# Power_Switching_Circuit_rev2.net
KiCad netlist of a schematic drawn in EAGLE
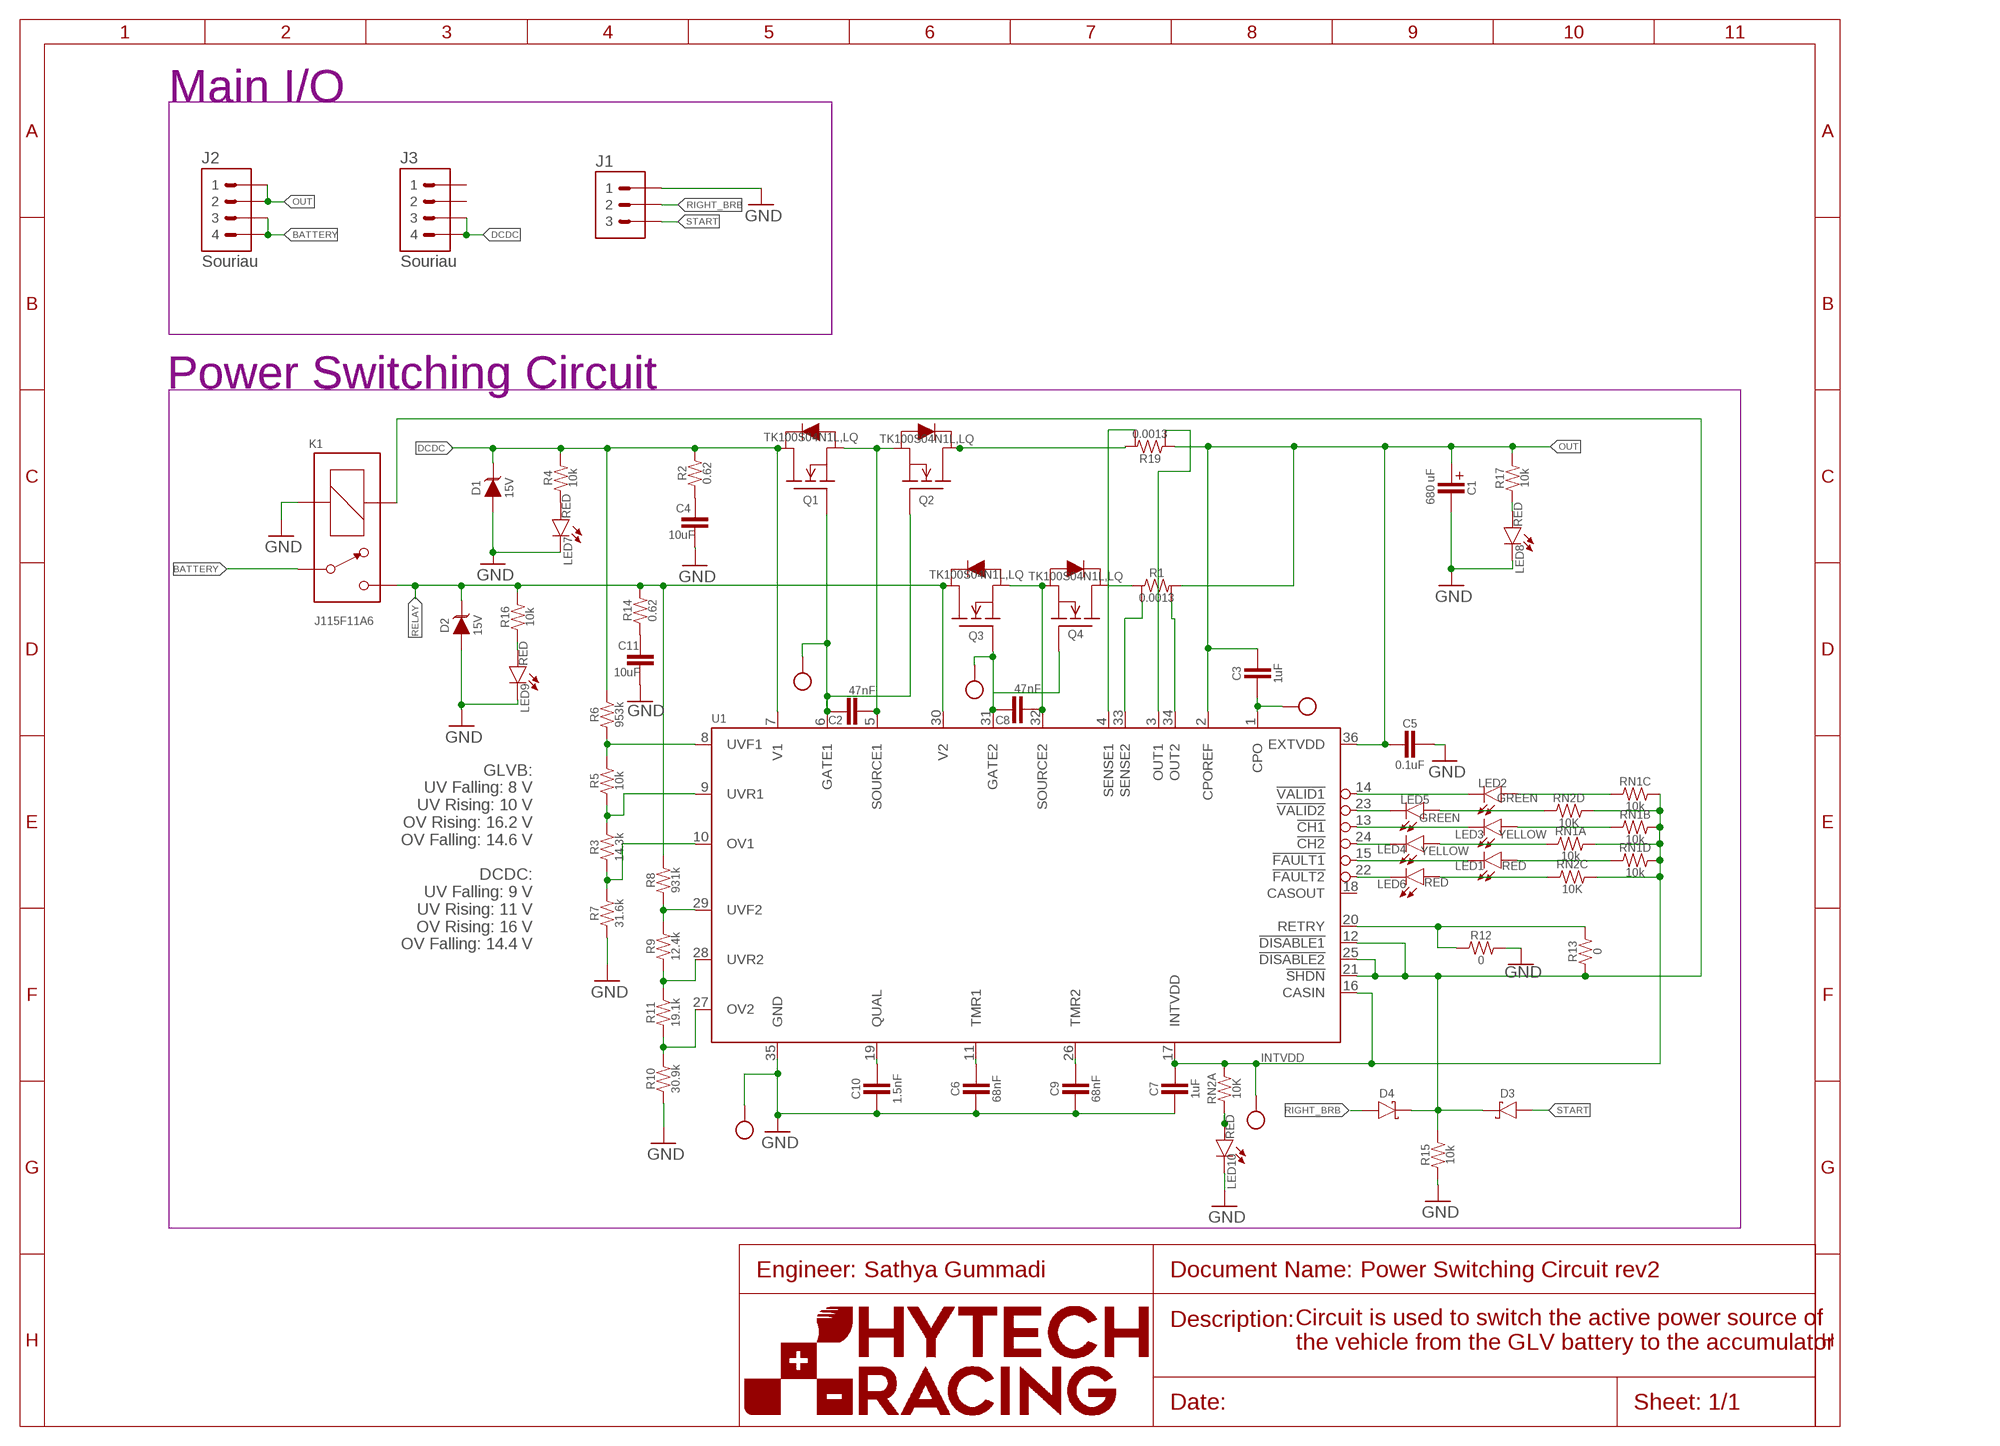
[diagram p0: schematic, sheet 1]

(export (version "E")
  (design (tool "Eeschema 10.0.6"))
  (components
    (comp (ref "C1")
      (value "CAPACITOR_POLARIZED")
      (footprint "eagle-import:EEE-FK1H681AM")
      (libsource (lib "eagle-import") (part "CAPACITOR_POLARIZED"))
    )
    (comp (ref "C2")
      (value "47nF")
      (footprint "eagle-import:0603-CAP@1")
      (libsource (lib "eagle-import") (part "CAP0603-CAP"))
    )
    (comp (ref "C3")
      (value "1uF")
      (footprint "eagle-import:0805")
      (libsource (lib "eagle-import") (part "CAP0805"))
    )
    (comp (ref "C4")
      (value "10uF")
      (footprint "eagle-import:1206-CAP")
      (libsource (lib "eagle-import") (part "CAPACITOR_VALUE1206"))
    )
    (comp (ref "C5")
      (value "0.1uF")
      (footprint "eagle-import:0603-CAP@1")
      (libsource (lib "eagle-import") (part "CAP0603-CAP"))
    )
    (comp (ref "C6")
      (value "68nF")
      (footprint "eagle-import:0603-CAP@1")
      (libsource (lib "eagle-import") (part "CAP0603-CAP"))
    )
    (comp (ref "C7")
      (value "1uF")
      (footprint "eagle-import:0805")
      (libsource (lib "eagle-import") (part "CAP0805"))
    )
    (comp (ref "C8")
      (value "47nF")
      (footprint "eagle-import:0603-CAP@1")
      (libsource (lib "eagle-import") (part "CAP0603-CAP"))
    )
    (comp (ref "C9")
      (value "68nF")
      (footprint "eagle-import:0603-CAP@1")
      (libsource (lib "eagle-import") (part "CAP0603-CAP"))
    )
    (comp (ref "C10")
      (value "1.5nF")
      (footprint "eagle-import:0603-CAP@1")
      (libsource (lib "eagle-import") (part "CAP0603-CAP"))
    )
    (comp (ref "C11")
      (value "10uF")
      (footprint "eagle-import:1206-CAP")
      (libsource (lib "eagle-import") (part "CAPACITOR_VALUE1206"))
    )
    (comp (ref "D1")
      (value "TVS_15V")
      (footprint "eagle-import:SOT-23")
      (fields
        (field (name "MANUFACTURER") "Vishay General Semiconductor - Diodes Division")
        (field (name "MPN") "GSOT15-E3-08")
        (field (name "VOLTAGE") "15V")
      )
      (libsource (lib "eagle-import") (part "TVS_15V"))
    )
    (comp (ref "D2")
      (value "TVS_15V")
      (footprint "eagle-import:SOT-23")
      (fields
        (field (name "MANUFACTURER") "Vishay General Semiconductor - Diodes Division")
        (field (name "MPN") "GSOT15-E3-08")
        (field (name "VOLTAGE") "15V")
      )
      (libsource (lib "eagle-import") (part "TVS_15V"))
    )
    (comp (ref "D3")
      (value "SCHOTTKY")
      (footprint "eagle-import:CLP1608-2L")
      (fields
        (field (name "MANUFACTURER") "Vishay General Semiconductor - Diodes Division")
        (field (name "MPN") "VSKY20401608-G4-08")
      )
      (libsource (lib "eagle-import") (part "SCHOTTKY"))
    )
    (comp (ref "D4")
      (value "SCHOTTKY")
      (footprint "eagle-import:CLP1608-2L")
      (fields
        (field (name "MANUFACTURER") "Vishay General Semiconductor - Diodes Division")
        (field (name "MPN") "VSKY20401608-G4-08")
      )
      (libsource (lib "eagle-import") (part "SCHOTTKY"))
    )
    (comp (ref "J1")
      (value "CONNECTOR-3_")
      (footprint "eagle-import:SOURIAU_04-35")
      (libsource (lib "eagle-import") (part "CONNECTOR-3_?"))
    )
    (comp (ref "J2")
      (value "CONNECTOR-4_SOURIAU_")
      (footprint "eagle-import:SOURIAU_12-04")
      (fields
        (field (name "MODEL") "Souriau")
        (field (name "MANUFACTURER") "Souriau")
        (field (name "MPN") "8STA21204PN ")
      )
      (libsource (lib "eagle-import") (part "CONNECTOR-4_?_SOURIAU"))
    )
    (comp (ref "J3")
      (value "CONNECTOR-4_SOURIAU_")
      (footprint "eagle-import:SOURIAU_12-04")
      (fields
        (field (name "MODEL") "Souriau")
        (field (name "MANUFACTURER") "Souriau")
        (field (name "MPN") "8STA21204PN ")
      )
      (libsource (lib "eagle-import") (part "CONNECTOR-4_?_SOURIAU"))
    )
    (comp (ref "K1")
      (value "J115F11A6")
      (footprint "eagle-import:J115F11A_6_")
      (libsource (lib "eagle-import") (part "J115F11A6"))
    )
    (comp (ref "LED1")
      (value "RED")
      (footprint "eagle-import:LED-603")
      (libsource (lib "eagle-import") (part "LED-0603"))
    )
    (comp (ref "LED2")
      (value "GREEN")
      (footprint "eagle-import:LED-603")
      (libsource (lib "eagle-import") (part "LED-0603"))
    )
    (comp (ref "LED3")
      (value "YELLOW")
      (footprint "eagle-import:LED-603")
      (libsource (lib "eagle-import") (part "LED-0603"))
    )
    (comp (ref "LED4")
      (value "YELLOW")
      (footprint "eagle-import:LED-603")
      (libsource (lib "eagle-import") (part "LED-0603"))
    )
    (comp (ref "LED5")
      (value "GREEN")
      (footprint "eagle-import:LED-603")
      (libsource (lib "eagle-import") (part "LED-0603"))
    )
    (comp (ref "LED6")
      (value "RED")
      (footprint "eagle-import:LED-603")
      (libsource (lib "eagle-import") (part "LED-0603"))
    )
    (comp (ref "LED7")
      (value "RED")
      (footprint "eagle-import:LED-603")
      (libsource (lib "eagle-import") (part "LED-0603"))
    )
    (comp (ref "LED8")
      (value "RED")
      (footprint "eagle-import:LED-603")
      (libsource (lib "eagle-import") (part "LED-0603"))
    )
    (comp (ref "LED9")
      (value "RED")
      (footprint "eagle-import:LED-603")
      (libsource (lib "eagle-import") (part "LED-0603"))
    )
    (comp (ref "LED10")
      (value "RED")
      (footprint "eagle-import:LED-603")
      (libsource (lib "eagle-import") (part "LED-0603"))
    )
    (comp (ref "Q1")
      (value "TRANSISTOR_N_MOS_2-7K1S_TK100S04N1L,LQ")
      (footprint "eagle-import:DPAK(2-7K1S)")
      (fields
        (field (name "MANUFACTURER") "Toshiba Semiconductor and Storage")
        (field (name "MPN") "TK100S04N1L,LQ")
      )
      (libsource (lib "eagle-import") (part "TRANSISTOR_N_MOS_?_2-7K1STK100S04N1L,LQ"))
    )
    (comp (ref "Q2")
      (value "TRANSISTOR_N_MOS_2-7K1S_TK100S04N1L,LQ")
      (footprint "eagle-import:DPAK(2-7K1S)")
      (fields
        (field (name "MANUFACTURER") "Toshiba Semiconductor and Storage")
        (field (name "MPN") "TK100S04N1L,LQ")
      )
      (libsource (lib "eagle-import") (part "TRANSISTOR_N_MOS_?_2-7K1STK100S04N1L,LQ"))
    )
    (comp (ref "Q3")
      (value "TRANSISTOR_N_MOS_2-7K1S_TK100S04N1L,LQ")
      (footprint "eagle-import:DPAK(2-7K1S)")
      (fields
        (field (name "MANUFACTURER") "Toshiba Semiconductor and Storage")
        (field (name "MPN") "TK100S04N1L,LQ")
      )
      (libsource (lib "eagle-import") (part "TRANSISTOR_N_MOS_?_2-7K1STK100S04N1L,LQ"))
    )
    (comp (ref "Q4")
      (value "TRANSISTOR_N_MOS_2-7K1S_TK100S04N1L,LQ")
      (footprint "eagle-import:DPAK(2-7K1S)")
      (fields
        (field (name "MANUFACTURER") "Toshiba Semiconductor and Storage")
        (field (name "MPN") "TK100S04N1L,LQ")
      )
      (libsource (lib "eagle-import") (part "TRANSISTOR_N_MOS_?_2-7K1STK100S04N1L,LQ"))
    )
    (comp (ref "R1")
      (value "RESISTOR_SENSE")
      (footprint "eagle-import:WSL2726")
      (fields (field (name "RESISTANCE") "0.0013") (field (name "MPN") "WSL2726"))
      (libsource (lib "eagle-import") (part "RESISTOR_SENSE"))
    )
    (comp (ref "R2")
      (value "0.62")
      (footprint "eagle-import:0805")
      (libsource (lib "eagle-import") (part "RESISTOR0805"))
    )
    (comp (ref "R3")
      (value "14.3k")
      (footprint "eagle-import:0603-RES")
      (libsource (lib "eagle-import") (part "RESISTOR0603"))
    )
    (comp (ref "R4")
      (value "10k")
      (footprint "eagle-import:0603-RES")
      (libsource (lib "eagle-import") (part "RESISTOR0603"))
    )
    (comp (ref "R5")
      (value "10k")
      (footprint "eagle-import:0603-RES")
      (libsource (lib "eagle-import") (part "RESISTOR0603"))
    )
    (comp (ref "R6")
      (value "953k")
      (footprint "eagle-import:0603-RES")
      (libsource (lib "eagle-import") (part "RESISTOR0603"))
    )
    (comp (ref "R7")
      (value "31.6k")
      (footprint "eagle-import:0603-RES")
      (libsource (lib "eagle-import") (part "RESISTOR0603"))
    )
    (comp (ref "R8")
      (value "931k")
      (footprint "eagle-import:0603-RES")
      (libsource (lib "eagle-import") (part "RESISTOR0603"))
    )
    (comp (ref "R9")
      (value "12.4k")
      (footprint "eagle-import:0603-RES")
      (libsource (lib "eagle-import") (part "RESISTOR0603"))
    )
    (comp (ref "R10")
      (value "30.9k")
      (footprint "eagle-import:0603-RES")
      (libsource (lib "eagle-import") (part "RESISTOR0603"))
    )
    (comp (ref "R11")
      (value "19.1k")
      (footprint "eagle-import:0603-RES")
      (libsource (lib "eagle-import") (part "RESISTOR0603"))
    )
    (comp (ref "R12")
      (value "0")
      (footprint "eagle-import:0603-RES")
      (libsource (lib "eagle-import") (part "RESISTOR0603"))
    )
    (comp (ref "R13")
      (value "0")
      (footprint "eagle-import:0603-RES")
      (libsource (lib "eagle-import") (part "RESISTOR0603"))
    )
    (comp (ref "R14")
      (value "0.62")
      (footprint "eagle-import:0805")
      (libsource (lib "eagle-import") (part "RESISTOR0805"))
    )
    (comp (ref "R15")
      (value "10k")
      (footprint "eagle-import:0603-RES")
      (libsource (lib "eagle-import") (part "RESISTOR0603"))
    )
    (comp (ref "R16")
      (value "10k")
      (footprint "eagle-import:0603-RES")
      (libsource (lib "eagle-import") (part "RESISTOR0603"))
    )
    (comp (ref "R17")
      (value "10k")
      (footprint "eagle-import:0603-RES")
      (libsource (lib "eagle-import") (part "RESISTOR0603"))
    )
    (comp (ref "R19")
      (value "RESISTOR_SENSE")
      (footprint "eagle-import:WSL2726")
      (fields (field (name "RESISTANCE") "0.0013") (field (name "MPN") "WSL2726"))
      (libsource (lib "eagle-import") (part "RESISTOR_SENSE"))
    )
    (comp (ref "RN1")
      (value "RESISTOR_NETWORK_4_10K")
      (footprint "eagle-import:YC_TC164")
      (fields (field (name "RESISTANCE") "10k"))
      (libsource (lib "eagle-import") (part "HyTechDevices - Copy_RESISTOR_NETWORK_4_10K"))
    )
    (comp (ref "RN2")
      (value "RESISTOR_NETWORK_4_10K")
      (footprint "eagle-import:1206-RES")
      (fields
        (field (name "MANUFACTURER") "Yageo")
        (field (name "MPN") "TC164-FR-0710KL")
        (field (name "POWER") "1/16W")
        (field (name "RESISTANCE") "10K")
      )
      (libsource (lib "eagle-import") (part "RESISTOR_NETWORK_4_10K"))
    )
    (comp (ref "U$7")
      (value "TEST_POINTMICRO_MINIATURE")
      (footprint "eagle-import:MICRO_MINIATURE")
      (libsource (lib "eagle-import") (part "TEST_POINTMICRO_MINIATURE"))
    )
    (comp (ref "U$8")
      (value "TEST_POINTMICRO_MINIATURE")
      (footprint "eagle-import:MICRO_MINIATURE")
      (libsource (lib "eagle-import") (part "TEST_POINTMICRO_MINIATURE"))
    )
    (comp (ref "U$9")
      (value "TEST_POINTMICRO_MINIATURE")
      (footprint "eagle-import:MICRO_MINIATURE")
      (libsource (lib "eagle-import") (part "TEST_POINTMICRO_MINIATURE"))
    )
    (comp (ref "U$10")
      (value "TEST_POINTMICRO_MINIATURE")
      (footprint "eagle-import:MICRO_MINIATURE")
      (libsource (lib "eagle-import") (part "TEST_POINTMICRO_MINIATURE"))
    )
    (comp (ref "U$11")
      (value "TEST_POINTMICRO_MINIATURE")
      (footprint "eagle-import:MICRO_MINIATURE")
      (libsource (lib "eagle-import") (part "TEST_POINTMICRO_MINIATURE"))
    )
    (comp (ref "U1")
      (value "LTC4421")
      (footprint "eagle-import:SSOP-36")
      (libsource (lib "eagle-import") (part "LTC4421"))
    )
  )
  (nets
    (net (code "1") (name "/INTVDD") (class "Default")
      (node (ref "C7") (pin "1") (pinfunction "1_1") (pintype "passive"))
      (node (ref "RN1") (pin "5") (pinfunction "2_5") (pintype "passive"))
      (node (ref "RN1") (pin "6") (pinfunction "2_6") (pintype "passive"))
      (node (ref "RN1") (pin "7") (pinfunction "2_7") (pintype "passive"))
      (node (ref "RN1") (pin "8") (pinfunction "2_8") (pintype "passive"))
      (node (ref "RN2") (pin "5") (pinfunction "2_5") (pintype "passive"))
      (node (ref "RN2") (pin "6") (pinfunction "2_6") (pintype "passive"))
      (node (ref "RN2") (pin "8") (pinfunction "2_8") (pintype "passive"))
      (node (ref "U$8") (pin "P$1") (pinfunction "P$1_P$1") (pintype "bidirectional"))
      (node (ref "U1") (pin "16") (pinfunction "CASIN_16") (pintype "input"))
      (node (ref "U1") (pin "17") (pinfunction "INTVDD_17") (pintype "power_in"))
    )
    (net (code "2") (name "BATTERY") (class "Default")
      (node (ref "J2") (pin "3") (pinfunction "3_3") (pintype "passive"))
      (node (ref "J2") (pin "4") (pinfunction "4_4") (pintype "passive"))
      (node (ref "K1") (pin "CONTACT1") (pinfunction "P_CONTACT1") (pintype "bidirectional"))
    )
    (net (code "3") (name "DCDC") (class "Default")
      (node (ref "D1") (pin "3") (pinfunction "C_3") (pintype "passive"))
      (node (ref "J3") (pin "3") (pinfunction "3_3") (pintype "passive"))
      (node (ref "J3") (pin "4") (pinfunction "4_4") (pintype "passive"))
      (node (ref "Q1") (pin "2") (pinfunction "D_2") (pintype "passive"))
      (node (ref "R2") (pin "2") (pinfunction "2_2") (pintype "passive"))
      (node (ref "R4") (pin "2") (pinfunction "2_2") (pintype "passive"))
      (node (ref "R6") (pin "2") (pinfunction "2_2") (pintype "passive"))
      (node (ref "U1") (pin "7") (pinfunction "V1_7") (pintype "input"))
    )
    (net (code "4") (name "GND") (class "Default")
      (node (ref "C1") (pin "P$2") (pinfunction "MINUS_P$2") (pintype "passive"))
      (node (ref "C10") (pin "2") (pinfunction "2_2") (pintype "passive"))
      (node (ref "C11") (pin "2") (pinfunction "2_2") (pintype "passive"))
      (node (ref "C4") (pin "2") (pinfunction "2_2") (pintype "passive"))
      (node (ref "C5") (pin "1") (pinfunction "1_1") (pintype "passive"))
      (node (ref "C6") (pin "2") (pinfunction "2_2") (pintype "passive"))
      (node (ref "C7") (pin "2") (pinfunction "2_2") (pintype "passive"))
      (node (ref "C9") (pin "2") (pinfunction "2_2") (pintype "passive"))
      (node (ref "D1") (pin "1") (pinfunction "A_1") (pintype "passive"))
      (node (ref "D2") (pin "1") (pinfunction "A_1") (pintype "passive"))
      (node (ref "J1") (pin "A") (pinfunction "1_A") (pintype "passive"))
      (node (ref "K1") (pin "COIL2") (pinfunction "COIL-_COIL2") (pintype "bidirectional"))
      (node (ref "LED10") (pin "C") (pinfunction "C_C") (pintype "passive"))
      (node (ref "LED7") (pin "C") (pinfunction "C_C") (pintype "passive"))
      (node (ref "LED8") (pin "C") (pinfunction "C_C") (pintype "passive"))
      (node (ref "LED9") (pin "C") (pinfunction "C_C") (pintype "passive"))
      (node (ref "R10") (pin "1") (pinfunction "1_1") (pintype "passive"))
      (node (ref "R12") (pin "2") (pinfunction "2_2") (pintype "passive"))
      (node (ref "R15") (pin "1") (pinfunction "1_1") (pintype "passive"))
      (node (ref "R7") (pin "1") (pinfunction "1_1") (pintype "passive"))
      (node (ref "U$11") (pin "P$1") (pinfunction "P$1_P$1") (pintype "bidirectional"))
      (node (ref "U1") (pin "35") (pinfunction "GND_35") (pintype "power_in"))
    )
    (net (code "5") (name "Net-(C4-Pad1)") (class "Default")
      (node (ref "C4") (pin "1") (pinfunction "1_1") (pintype "passive"))
      (node (ref "R2") (pin "1") (pinfunction "1_1") (pintype "passive"))
    )
    (net (code "6") (name "Net-(C11-Pad1)") (class "Default")
      (node (ref "C11") (pin "1") (pinfunction "1_1") (pintype "passive"))
      (node (ref "R14") (pin "1") (pinfunction "1_1") (pintype "passive"))
    )
    (net (code "7") (name "Net-(D3-C)") (class "Default")
      (node (ref "D3") (pin "2") (pinfunction "C_2") (pintype "passive"))
      (node (ref "D4") (pin "2") (pinfunction "C_2") (pintype "passive"))
      (node (ref "K1") (pin "COIL1") (pinfunction "COIL+_COIL1") (pintype "bidirectional"))
      (node (ref "R13") (pin "1") (pinfunction "1_1") (pintype "passive"))
      (node (ref "R15") (pin "2") (pinfunction "2_2") (pintype "passive"))
      (node (ref "U1") (pin "12") (pinfunction "~{DISABLE1}_12") (pintype "input"))
      (node (ref "U1") (pin "21") (pinfunction "~{SHDN}_21") (pintype "input"))
      (node (ref "U1") (pin "25") (pinfunction "~{DISABLE2}_25") (pintype "input"))
    )
    (net (code "8") (name "Net-(LED4-PadA)") (class "Default")
      (node (ref "LED4") (pin "A") (pinfunction "A_A") (pintype "passive"))
      (node (ref "RN1") (pin "1") (pinfunction "1_1") (pintype "passive"))
    )
    (net (code "9") (name "Net-(LED7-PadA)") (class "Default")
      (node (ref "LED7") (pin "A") (pinfunction "A_A") (pintype "passive"))
      (node (ref "R4") (pin "1") (pinfunction "1_1") (pintype "passive"))
    )
    (net (code "10") (name "Net-(LED8-PadA)") (class "Default")
      (node (ref "LED8") (pin "A") (pinfunction "A_A") (pintype "passive"))
      (node (ref "R17") (pin "1") (pinfunction "1_1") (pintype "passive"))
    )
    (net (code "11") (name "Net-(LED9-PadA)") (class "Default")
      (node (ref "LED9") (pin "A") (pinfunction "A_A") (pintype "passive"))
      (node (ref "R16") (pin "1") (pinfunction "1_1") (pintype "passive"))
    )
    (net (code "12") (name "Net-(LED10-PadA)") (class "Default")
      (node (ref "LED10") (pin "A") (pinfunction "A_A") (pintype "passive"))
      (node (ref "RN2") (pin "1") (pinfunction "1_1") (pintype "passive"))
    )
    (net (code "13") (name "Net-(Q1-G)") (class "Default")
      (node (ref "C2") (pin "2") (pinfunction "2_2") (pintype "passive"))
      (node (ref "Q1") (pin "1") (pinfunction "G_1") (pintype "passive"))
      (node (ref "Q2") (pin "1") (pinfunction "G_1") (pintype "passive"))
      (node (ref "U$10") (pin "P$1") (pinfunction "P$1_P$1") (pintype "bidirectional"))
      (node (ref "U1") (pin "6") (pinfunction "GATE1_6") (pintype "input"))
    )
    (net (code "14") (name "Net-(Q1-S)") (class "Default")
      (node (ref "C2") (pin "1") (pinfunction "1_1") (pintype "passive"))
      (node (ref "Q1") (pin "3") (pinfunction "S_3") (pintype "passive"))
      (node (ref "Q2") (pin "3") (pinfunction "S_3") (pintype "passive"))
      (node (ref "U1") (pin "5") (pinfunction "SOURCE1_5") (pintype "input"))
    )
    (net (code "15") (name "Net-(Q2-D)") (class "Default")
      (node (ref "Q2") (pin "2") (pinfunction "D_2") (pintype "passive"))
      (node (ref "R19") (pin "2") (pinfunction "2_2") (pintype "passive"))
    )
    (net (code "16") (name "Net-(Q3-G)") (class "Default")
      (node (ref "C8") (pin "2") (pinfunction "2_2") (pintype "passive"))
      (node (ref "Q3") (pin "1") (pinfunction "G_1") (pintype "passive"))
      (node (ref "Q4") (pin "1") (pinfunction "G_1") (pintype "passive"))
      (node (ref "U$7") (pin "P$1") (pinfunction "P$1_P$1") (pintype "bidirectional"))
      (node (ref "U1") (pin "31") (pinfunction "GATE2_31") (pintype "input"))
    )
    (net (code "17") (name "Net-(Q3-S)") (class "Default")
      (node (ref "C8") (pin "1") (pinfunction "1_1") (pintype "passive"))
      (node (ref "Q3") (pin "3") (pinfunction "S_3") (pintype "passive"))
      (node (ref "Q4") (pin "3") (pinfunction "S_3") (pintype "passive"))
      (node (ref "U1") (pin "32") (pinfunction "SOURCE2_32") (pintype "input"))
    )
    (net (code "18") (name "Net-(Q4-D)") (class "Default")
      (node (ref "Q4") (pin "2") (pinfunction "D_2") (pintype "passive"))
      (node (ref "R1") (pin "1") (pinfunction "1_1") (pintype "passive"))
    )
    (net (code "19") (name "Net-(RN1B-1)") (class "Default")
      (node (ref "LED3") (pin "A") (pinfunction "A_A") (pintype "passive"))
      (node (ref "RN1") (pin "2") (pinfunction "1_2") (pintype "passive"))
    )
    (net (code "20") (name "Net-(RN1C-1)") (class "Default")
      (node (ref "LED2") (pin "A") (pinfunction "A_A") (pintype "passive"))
      (node (ref "RN1") (pin "3") (pinfunction "1_3") (pintype "passive"))
    )
    (net (code "21") (name "Net-(RN1D-1)") (class "Default")
      (node (ref "LED1") (pin "A") (pinfunction "A_A") (pintype "passive"))
      (node (ref "RN1") (pin "4") (pinfunction "1_4") (pintype "passive"))
    )
    (net (code "22") (name "Net-(RN2C-1)") (class "Default")
      (node (ref "LED6") (pin "A") (pinfunction "A_A") (pintype "passive"))
      (node (ref "RN2") (pin "3") (pinfunction "1_3") (pintype "passive"))
    )
    (net (code "23") (name "Net-(RN2D-1)") (class "Default")
      (node (ref "LED5") (pin "A") (pinfunction "A_A") (pintype "passive"))
      (node (ref "RN2") (pin "4") (pinfunction "1_4") (pintype "passive"))
    )
    (net (code "24") (name "Net-(U1-CPO)") (class "Default")
      (node (ref "C3") (pin "2") (pinfunction "2_2") (pintype "passive"))
      (node (ref "U$9") (pin "P$1") (pinfunction "P$1_P$1") (pintype "bidirectional"))
      (node (ref "U1") (pin "1") (pinfunction "CPO_1") (pintype "input"))
    )
    (net (code "25") (name "Net-(U1-OUT1)") (class "Default")
      (node (ref "R19") (pin "3") (pinfunction "3_3") (pintype "passive"))
      (node (ref "U1") (pin "3") (pinfunction "OUT1_3") (pintype "input"))
    )
    (net (code "26") (name "Net-(U1-OUT2)") (class "Default")
      (node (ref "R1") (pin "4") (pinfunction "4_4") (pintype "passive"))
      (node (ref "U1") (pin "34") (pinfunction "OUT2_34") (pintype "input"))
    )
    (net (code "27") (name "Net-(U1-OV1)") (class "Default")
      (node (ref "R3") (pin "1") (pinfunction "1_1") (pintype "passive"))
      (node (ref "R7") (pin "2") (pinfunction "2_2") (pintype "passive"))
      (node (ref "U1") (pin "10") (pinfunction "OV1_10") (pintype "input"))
    )
    (net (code "28") (name "Net-(U1-OV2)") (class "Default")
      (node (ref "R10") (pin "2") (pinfunction "2_2") (pintype "passive"))
      (node (ref "R11") (pin "1") (pinfunction "1_1") (pintype "passive"))
      (node (ref "U1") (pin "27") (pinfunction "OV2_27") (pintype "input"))
    )
    (net (code "29") (name "Net-(U1-QUAL)") (class "Default")
      (node (ref "C10") (pin "1") (pinfunction "1_1") (pintype "passive"))
      (node (ref "U1") (pin "19") (pinfunction "QUAL_19") (pintype "bidirectional"))
    )
    (net (code "30") (name "Net-(U1-RETRY)") (class "Default")
      (node (ref "R12") (pin "1") (pinfunction "1_1") (pintype "passive"))
      (node (ref "R13") (pin "2") (pinfunction "2_2") (pintype "passive"))
      (node (ref "U1") (pin "20") (pinfunction "RETRY_20") (pintype "input"))
    )
    (net (code "31") (name "Net-(U1-SENSE1)") (class "Default")
      (node (ref "R19") (pin "4") (pinfunction "4_4") (pintype "passive"))
      (node (ref "U1") (pin "4") (pinfunction "SENSE1_4") (pintype "input"))
    )
    (net (code "32") (name "Net-(U1-SENSE2)") (class "Default")
      (node (ref "R1") (pin "3") (pinfunction "3_3") (pintype "passive"))
      (node (ref "U1") (pin "33") (pinfunction "SENSE2_33") (pintype "input"))
    )
    (net (code "33") (name "Net-(U1-TMR1)") (class "Default")
      (node (ref "C6") (pin "1") (pinfunction "1_1") (pintype "passive"))
      (node (ref "U1") (pin "11") (pinfunction "TMR1_11") (pintype "bidirectional"))
    )
    (net (code "34") (name "Net-(U1-TMR2)") (class "Default")
      (node (ref "C9") (pin "1") (pinfunction "1_1") (pintype "passive"))
      (node (ref "U1") (pin "26") (pinfunction "TMR2_26") (pintype "bidirectional"))
    )
    (net (code "35") (name "Net-(U1-UVF1)") (class "Default")
      (node (ref "R5") (pin "2") (pinfunction "2_2") (pintype "passive"))
      (node (ref "R6") (pin "1") (pinfunction "1_1") (pintype "passive"))
      (node (ref "U1") (pin "8") (pinfunction "UVF1_8") (pintype "input"))
    )
    (net (code "36") (name "Net-(U1-UVF2)") (class "Default")
      (node (ref "R8") (pin "1") (pinfunction "1_1") (pintype "passive"))
      (node (ref "R9") (pin "2") (pinfunction "2_2") (pintype "passive"))
      (node (ref "U1") (pin "29") (pinfunction "UVF2_29") (pintype "input"))
    )
    (net (code "37") (name "Net-(U1-UVR1)") (class "Default")
      (node (ref "R3") (pin "2") (pinfunction "2_2") (pintype "passive"))
      (node (ref "R5") (pin "1") (pinfunction "1_1") (pintype "passive"))
      (node (ref "U1") (pin "9") (pinfunction "UVR1_9") (pintype "input"))
    )
    (net (code "38") (name "Net-(U1-UVR2)") (class "Default")
      (node (ref "R11") (pin "2") (pinfunction "2_2") (pintype "passive"))
      (node (ref "R9") (pin "1") (pinfunction "1_1") (pintype "passive"))
      (node (ref "U1") (pin "28") (pinfunction "UVR2_28") (pintype "input"))
    )
    (net (code "39") (name "Net-(U1-~{CH1})") (class "Default")
      (node (ref "LED3") (pin "C") (pinfunction "C_C") (pintype "passive"))
      (node (ref "U1") (pin "13") (pinfunction "~{CH1}_13") (pintype "open_collector"))
    )
    (net (code "40") (name "Net-(U1-~{CH2})") (class "Default")
      (node (ref "LED4") (pin "C") (pinfunction "C_C") (pintype "passive"))
      (node (ref "U1") (pin "24") (pinfunction "~{CH2}_24") (pintype "open_collector"))
    )
    (net (code "41") (name "Net-(U1-~{FAULT1})") (class "Default")
      (node (ref "LED1") (pin "C") (pinfunction "C_C") (pintype "passive"))
      (node (ref "U1") (pin "15") (pinfunction "~{FAULT1}_15") (pintype "open_collector"))
    )
    (net (code "42") (name "Net-(U1-~{FAULT2})") (class "Default")
      (node (ref "LED6") (pin "C") (pinfunction "C_C") (pintype "passive"))
      (node (ref "U1") (pin "22") (pinfunction "~{FAULT2}_22") (pintype "open_collector"))
    )
    (net (code "43") (name "Net-(U1-~{VALID1})") (class "Default")
      (node (ref "LED2") (pin "C") (pinfunction "C_C") (pintype "passive"))
      (node (ref "U1") (pin "14") (pinfunction "~{VALID1}_14") (pintype "open_collector"))
    )
    (net (code "44") (name "Net-(U1-~{VALID2})") (class "Default")
      (node (ref "LED5") (pin "C") (pinfunction "C_C") (pintype "passive"))
      (node (ref "U1") (pin "23") (pinfunction "~{VALID2}_23") (pintype "open_collector"))
    )
    (net (code "45") (name "OUT") (class "Default")
      (node (ref "C1") (pin "P$1") (pinfunction "PLUS_P$1") (pintype "passive"))
      (node (ref "C3") (pin "1") (pinfunction "1_1") (pintype "passive"))
      (node (ref "C5") (pin "2") (pinfunction "2_2") (pintype "passive"))
      (node (ref "J2") (pin "1") (pinfunction "1_1") (pintype "passive"))
      (node (ref "J2") (pin "2") (pinfunction "2_2") (pintype "passive"))
      (node (ref "R1") (pin "2") (pinfunction "2_2") (pintype "passive"))
      (node (ref "R17") (pin "2") (pinfunction "2_2") (pintype "passive"))
      (node (ref "R19") (pin "1") (pinfunction "1_1") (pintype "passive"))
      (node (ref "U1") (pin "2") (pinfunction "CPOREF_2") (pintype "input"))
      (node (ref "U1") (pin "36") (pinfunction "EXTVDD_36") (pintype "power_in"))
    )
    (net (code "46") (name "RELAY") (class "Default")
      (node (ref "D2") (pin "3") (pinfunction "C_3") (pintype "passive"))
      (node (ref "K1") (pin "CONTACT2") (pinfunction "S_CONTACT2") (pintype "bidirectional"))
      (node (ref "Q3") (pin "2") (pinfunction "D_2") (pintype "passive"))
      (node (ref "R14") (pin "2") (pinfunction "2_2") (pintype "passive"))
      (node (ref "R16") (pin "2") (pinfunction "2_2") (pintype "passive"))
      (node (ref "R8") (pin "2") (pinfunction "2_2") (pintype "passive"))
      (node (ref "U1") (pin "30") (pinfunction "V2_30") (pintype "input"))
    )
    (net (code "47") (name "RIGHT_BRB") (class "Default")
      (node (ref "D4") (pin "1") (pinfunction "A_1") (pintype "passive"))
      (node (ref "J1") (pin "B") (pinfunction "2_B") (pintype "passive"))
    )
    (net (code "48") (name "START") (class "Default")
      (node (ref "D3") (pin "1") (pinfunction "A_1") (pintype "passive"))
      (node (ref "J1") (pin "C") (pinfunction "3_C") (pintype "passive"))
    )
    (net (code "49") (name "unconnected-(J3-Pad1)") (class "Default")
      (node (ref "J3") (pin "1") (pinfunction "1_1") (pintype "passive"))
    )
    (net (code "50") (name "unconnected-(J3-Pad2)") (class "Default")
      (node (ref "J3") (pin "2") (pinfunction "2_2") (pintype "passive"))
    )
    (net (code "51") (name "unconnected-(U1-CASOUT-Pad18)") (class "Default")
      (node (ref "U1") (pin "18") (pinfunction "CASOUT_18") (pintype "output"))
    )
  )
)
